# nv-h5b.net
KiCad netlist of a schematic drawn in EAGLE
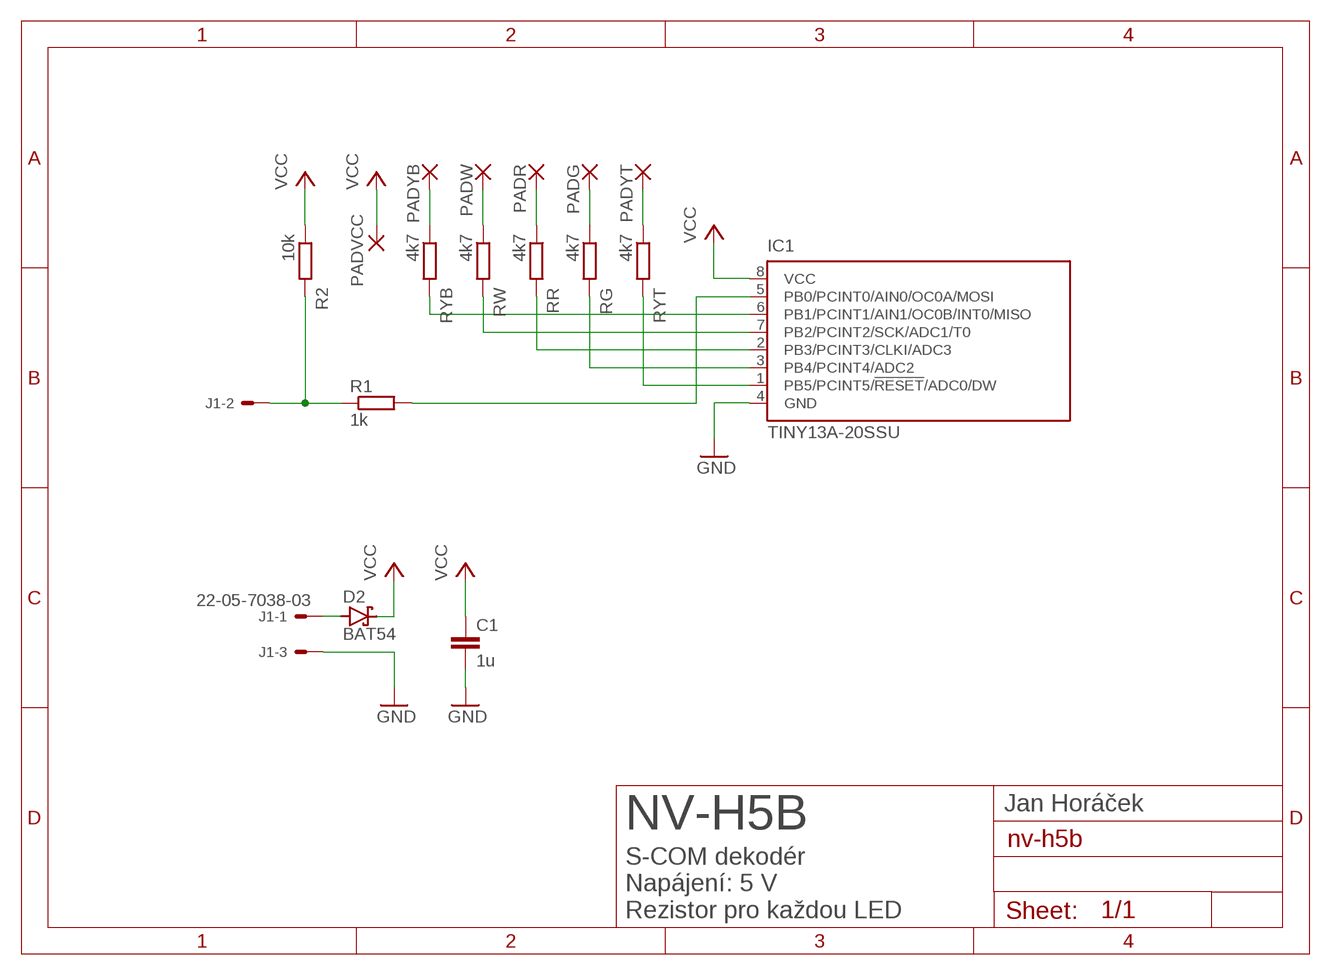
[diagram p0: schematic, sheet 1]

(export (version "E")
  (design (tool "Eeschema 10.0.6"))
  (components
    (comp (ref "C1")
      (value "1u")
      (footprint "eagle-import:C0805")
      (libsource (lib "eagle-import") (part "C-EUC0805"))
    )
    (comp (ref "D2")
      (value "BAT54")
      (footprint "eagle-import:SOT23")
      (libsource (lib "eagle-import") (part "BAT54"))
    )
    (comp (ref "IC1")
      (value "TINY13A-20SSU")
      (footprint "eagle-import:8S1")
      (fields (field (name "MPN") "ATTINY13-20SSU"))
      (libsource (lib "eagle-import") (part "TINY13SSU-20"))
    )
    (comp (ref "J1")
      (value "22-05-7038-03")
      (footprint "eagle-import:7395-03")
      (fields (field (name "MF") "MOLEX"))
      (libsource (lib "eagle-import") (part "22-?-0305-7038"))
    )
    (comp (ref "PADG")
      (value "SMD3")
      (footprint "eagle-import:SMD1,778-5,08")
      (libsource (lib "eagle-import") (part "SMD3"))
    )
    (comp (ref "PADR")
      (value "SMD3")
      (footprint "eagle-import:SMD1,778-5,08")
      (libsource (lib "eagle-import") (part "SMD3"))
    )
    (comp (ref "PADVCC")
      (value "SMD3")
      (footprint "eagle-import:SMD1,778-5,08")
      (libsource (lib "eagle-import") (part "SMD3"))
    )
    (comp (ref "PADW")
      (value "SMD3")
      (footprint "eagle-import:SMD1,778-5,08")
      (libsource (lib "eagle-import") (part "SMD3"))
    )
    (comp (ref "PADYB")
      (value "SMD3")
      (footprint "eagle-import:SMD1,778-5,08")
      (libsource (lib "eagle-import") (part "SMD3"))
    )
    (comp (ref "PADYT")
      (value "SMD3")
      (footprint "eagle-import:SMD1,778-5,08")
      (libsource (lib "eagle-import") (part "SMD3"))
    )
    (comp (ref "R1")
      (value "1k")
      (footprint "eagle-import:R0805")
      (libsource (lib "eagle-import") (part "R-EU_R0805"))
    )
    (comp (ref "R2")
      (value "10k")
      (footprint "eagle-import:R0805")
      (libsource (lib "eagle-import") (part "R-EU_R0805"))
    )
    (comp (ref "RG")
      (value "4k7")
      (footprint "eagle-import:R0805")
      (libsource (lib "eagle-import") (part "R-EU_R0805"))
    )
    (comp (ref "RR")
      (value "4k7")
      (footprint "eagle-import:R0805")
      (libsource (lib "eagle-import") (part "R-EU_R0805"))
    )
    (comp (ref "RW")
      (value "4k7")
      (footprint "eagle-import:R0805")
      (libsource (lib "eagle-import") (part "R-EU_R0805"))
    )
    (comp (ref "RYB")
      (value "4k7")
      (footprint "eagle-import:R0805")
      (libsource (lib "eagle-import") (part "R-EU_R0805"))
    )
    (comp (ref "RYT")
      (value "4k7")
      (footprint "eagle-import:R0805")
      (libsource (lib "eagle-import") (part "R-EU_R0805"))
    )
  )
  (nets
    (net (code "1") (name "GND") (class "Default")
      (node (ref "C1") (pin "2") (pinfunction "2_2") (pintype "passive"))
      (node (ref "IC1") (pin "4") (pinfunction "GND_4") (pintype "power_in"))
      (node (ref "J1") (pin "3") (pinfunction "S_3") (pintype "passive"))
    )
    (net (code "2") (name "Net-(D2-A)") (class "Default")
      (node (ref "D2") (pin "1") (pinfunction "A_1") (pintype "passive"))
      (node (ref "J1") (pin "1") (pinfunction "S_1") (pintype "passive"))
    )
    (net (code "3") (name "Net-(IC1-PB0{slash}PCINT0{slash}AIN0{slash}OC0A{slash}MOSI)") (class "Default")
      (node (ref "IC1") (pin "5") (pinfunction "PB0/PCINT0/AIN0/OC0A/MOSI_5") (pintype "bidirectional"))
      (node (ref "R1") (pin "2") (pinfunction "2_2") (pintype "passive"))
    )
    (net (code "4") (name "Net-(IC1-PB1{slash}PCINT1{slash}AIN1{slash}OC0B{slash}INT0{slash}MISO)") (class "Default")
      (node (ref "IC1") (pin "6") (pinfunction "PB1/PCINT1/AIN1/OC0B/INT0/MISO_6") (pintype "bidirectional"))
      (node (ref "RYB") (pin "2") (pinfunction "2_2") (pintype "passive"))
    )
    (net (code "5") (name "Net-(IC1-PB2{slash}PCINT2{slash}SCK{slash}ADC1{slash}T0)") (class "Default")
      (node (ref "IC1") (pin "7") (pinfunction "PB2/PCINT2/SCK/ADC1/T0_7") (pintype "bidirectional"))
      (node (ref "RW") (pin "2") (pinfunction "2_2") (pintype "passive"))
    )
    (net (code "6") (name "Net-(IC1-PB3{slash}PCINT3{slash}CLKI{slash}ADC3)") (class "Default")
      (node (ref "IC1") (pin "2") (pinfunction "PB3/PCINT3/CLKI/ADC3_2") (pintype "bidirectional"))
      (node (ref "RR") (pin "2") (pinfunction "2_2") (pintype "passive"))
    )
    (net (code "7") (name "Net-(IC1-PB4{slash}PCINT4{slash}ADC2)") (class "Default")
      (node (ref "IC1") (pin "3") (pinfunction "PB4/PCINT4/ADC2_3") (pintype "bidirectional"))
      (node (ref "RG") (pin "2") (pinfunction "2_2") (pintype "passive"))
    )
    (net (code "8") (name "Net-(IC1-PB5{slash}PCINT5{slash}~{RESET}{slash}ADC0{slash}DW)") (class "Default")
      (node (ref "IC1") (pin "1") (pinfunction "PB5/PCINT5/~{RESET}/ADC0/DW_1") (pintype "bidirectional"))
      (node (ref "RYT") (pin "2") (pinfunction "2_2") (pintype "passive"))
    )
    (net (code "9") (name "Net-(J1B-S)") (class "Default")
      (node (ref "J1") (pin "2") (pinfunction "S_2") (pintype "passive"))
      (node (ref "R1") (pin "1") (pinfunction "1_1") (pintype "passive"))
      (node (ref "R2") (pin "2") (pinfunction "2_2") (pintype "passive"))
    )
    (net (code "10") (name "Net-(PADG-P)") (class "Default")
      (node (ref "PADG") (pin "1") (pinfunction "P_1") (pintype "passive"))
      (node (ref "RG") (pin "1") (pinfunction "1_1") (pintype "passive"))
    )
    (net (code "11") (name "Net-(PADR-P)") (class "Default")
      (node (ref "PADR") (pin "1") (pinfunction "P_1") (pintype "passive"))
      (node (ref "RR") (pin "1") (pinfunction "1_1") (pintype "passive"))
    )
    (net (code "12") (name "Net-(PADW-P)") (class "Default")
      (node (ref "PADW") (pin "1") (pinfunction "P_1") (pintype "passive"))
      (node (ref "RW") (pin "1") (pinfunction "1_1") (pintype "passive"))
    )
    (net (code "13") (name "Net-(PADYB-P)") (class "Default")
      (node (ref "PADYB") (pin "1") (pinfunction "P_1") (pintype "passive"))
      (node (ref "RYB") (pin "1") (pinfunction "1_1") (pintype "passive"))
    )
    (net (code "14") (name "Net-(PADYT-P)") (class "Default")
      (node (ref "PADYT") (pin "1") (pinfunction "P_1") (pintype "passive"))
      (node (ref "RYT") (pin "1") (pinfunction "1_1") (pintype "passive"))
    )
    (net (code "15") (name "VCC") (class "Default")
      (node (ref "C1") (pin "1") (pinfunction "1_1") (pintype "passive"))
      (node (ref "D2") (pin "3") (pinfunction "C_3") (pintype "passive"))
      (node (ref "IC1") (pin "8") (pinfunction "VCC_8") (pintype "power_in"))
      (node (ref "PADVCC") (pin "1") (pinfunction "P_1") (pintype "passive"))
      (node (ref "R2") (pin "1") (pinfunction "1_1") (pintype "passive"))
    )
  )
)
